# XORXNOR.net
KiCad netlist of a schematic drawn in Altium Designer
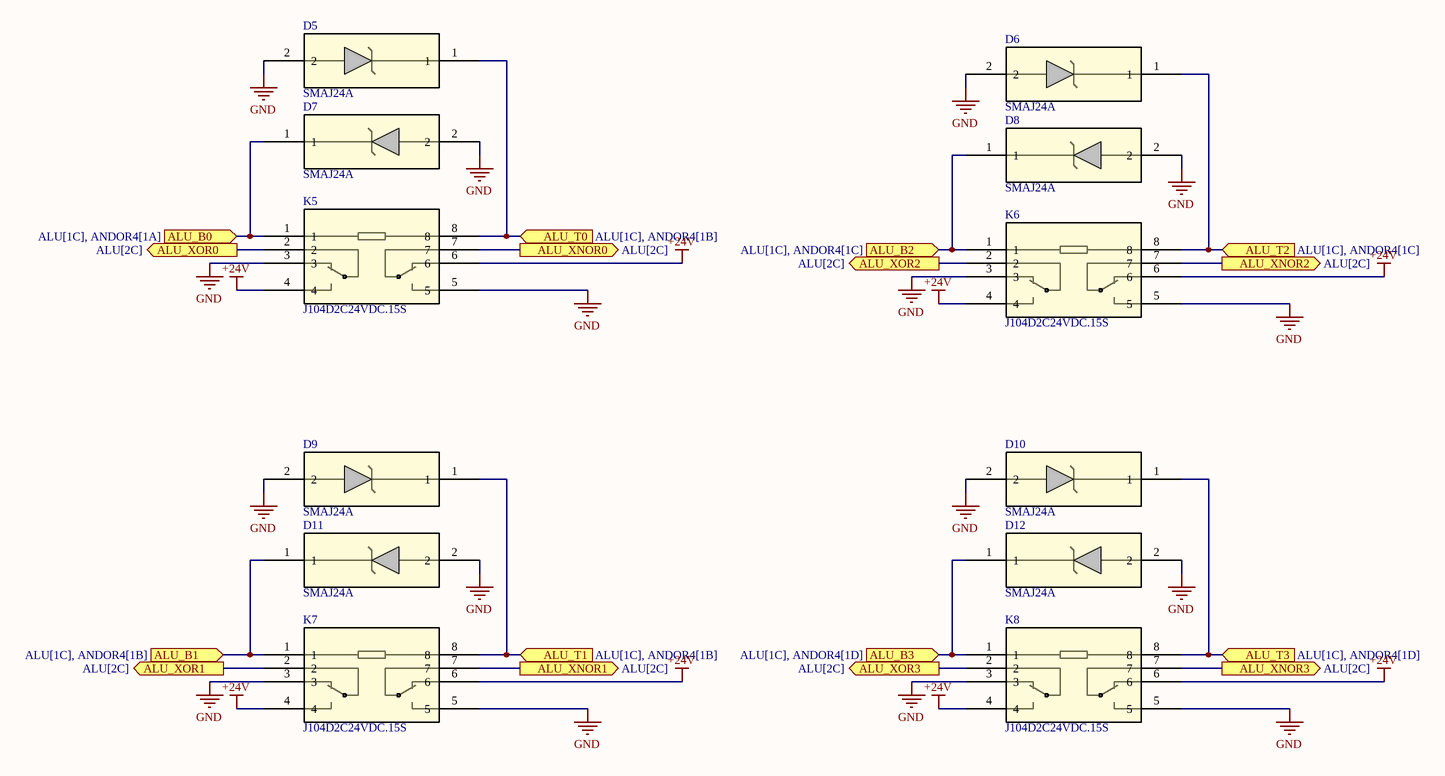
[diagram p0: XORXNOR.SchDoc]

(export (version "E")
  (design (tool "Eeschema 10.0.6"))
  (components
    (comp (ref "D5")
      (value "SMAJ24A")
      (footprint "DI SMAJ24A")
      (description "SMAJ Series 400 W 24 V Uni-Directional Surface Mount TVS Diode - DO-214AC")
      (fields (field (name "MANUFACTURER") "Littelfuse"))
      (libsource (lib "Schlib1") (part "DI SMAJ24A"))
    )
    (comp (ref "D6")
      (value "SMAJ24A")
      (footprint "DI SMAJ24A")
      (description "SMAJ Series 400 W 24 V Uni-Directional Surface Mount TVS Diode - DO-214AC")
      (fields (field (name "MANUFACTURER") "Littelfuse"))
      (libsource (lib "Schlib1") (part "DI SMAJ24A"))
    )
    (comp (ref "D7")
      (value "SMAJ24A")
      (footprint "DI SMAJ24A")
      (description "SMAJ Series 400 W 24 V Uni-Directional Surface Mount TVS Diode - DO-214AC")
      (fields (field (name "MANUFACTURER") "Littelfuse"))
      (libsource (lib "") (part "DI SMAJ24A_1"))
    )
    (comp (ref "D8")
      (value "SMAJ24A")
      (footprint "DI SMAJ24A")
      (description "SMAJ Series 400 W 24 V Uni-Directional Surface Mount TVS Diode - DO-214AC")
      (fields (field (name "MANUFACTURER") "Littelfuse"))
      (libsource (lib "") (part "DI SMAJ24A_1"))
    )
    (comp (ref "D9")
      (value "SMAJ24A")
      (footprint "DI SMAJ24A")
      (description "SMAJ Series 400 W 24 V Uni-Directional Surface Mount TVS Diode - DO-214AC")
      (fields (field (name "MANUFACTURER") "Littelfuse"))
      (libsource (lib "Schlib1") (part "DI SMAJ24A"))
    )
    (comp (ref "D10")
      (value "SMAJ24A")
      (footprint "DI SMAJ24A")
      (description "SMAJ Series 400 W 24 V Uni-Directional Surface Mount TVS Diode - DO-214AC")
      (fields (field (name "MANUFACTURER") "Littelfuse"))
      (libsource (lib "Schlib1") (part "DI SMAJ24A"))
    )
    (comp (ref "D11")
      (value "SMAJ24A")
      (footprint "DI SMAJ24A")
      (description "SMAJ Series 400 W 24 V Uni-Directional Surface Mount TVS Diode - DO-214AC")
      (fields (field (name "MANUFACTURER") "Littelfuse"))
      (libsource (lib "") (part "DI SMAJ24A_1"))
    )
    (comp (ref "D12")
      (value "SMAJ24A")
      (footprint "DI SMAJ24A")
      (description "SMAJ Series 400 W 24 V Uni-Directional Surface Mount TVS Diode - DO-214AC")
      (fields (field (name "MANUFACTURER") "Littelfuse"))
      (libsource (lib "") (part "DI SMAJ24A_1"))
    )
    (comp (ref "K5")
      (value "J104D2C24VDC.15S")
      (footprint "Relay J104D2C24VDC.15S")
      (description "Relay Ul Gen Purp DPDT 2C 24VDC")
      (fields (field (name "MANUFACTURER") "CIT Relay & Switch"))
      (libsource (lib "Schlib1") (part "Relay J104D2C24VDC.15S"))
    )
    (comp (ref "K6")
      (value "J104D2C24VDC.15S")
      (footprint "Relay J104D2C24VDC.15S")
      (description "Relay Ul Gen Purp DPDT 2C 24VDC")
      (fields (field (name "MANUFACTURER") "CIT Relay & Switch"))
      (libsource (lib "Schlib1") (part "Relay J104D2C24VDC.15S"))
    )
    (comp (ref "K7")
      (value "J104D2C24VDC.15S")
      (footprint "Relay J104D2C24VDC.15S")
      (description "Relay Ul Gen Purp DPDT 2C 24VDC")
      (fields (field (name "MANUFACTURER") "CIT Relay & Switch"))
      (libsource (lib "Schlib1") (part "Relay J104D2C24VDC.15S"))
    )
    (comp (ref "K8")
      (value "J104D2C24VDC.15S")
      (footprint "Relay J104D2C24VDC.15S")
      (description "Relay Ul Gen Purp DPDT 2C 24VDC")
      (fields (field (name "MANUFACTURER") "CIT Relay & Switch"))
      (libsource (lib "Schlib1") (part "Relay J104D2C24VDC.15S"))
    )
  )
  (nets
    (net (code "1") (name "+24V") (class "Default")
      (node (ref "K5") (pin "4") (pinfunction "4_4") (pintype "passive"))
      (node (ref "K5") (pin "6") (pinfunction "6_6") (pintype "passive"))
      (node (ref "K6") (pin "4") (pinfunction "4_4") (pintype "passive"))
      (node (ref "K6") (pin "6") (pinfunction "6_6") (pintype "passive"))
      (node (ref "K7") (pin "4") (pinfunction "4_4") (pintype "passive"))
      (node (ref "K7") (pin "6") (pinfunction "6_6") (pintype "passive"))
      (node (ref "K8") (pin "4") (pinfunction "4_4") (pintype "passive"))
      (node (ref "K8") (pin "6") (pinfunction "6_6") (pintype "passive"))
    )
    (net (code "2") (name "/ALU_B0") (class "Default")
      (node (ref "D7") (pin "1") (pinfunction "1_1") (pintype "passive"))
      (node (ref "K5") (pin "1") (pinfunction "1_1") (pintype "passive"))
    )
    (net (code "3") (name "/ALU_B1") (class "Default")
      (node (ref "D11") (pin "1") (pinfunction "1_1") (pintype "passive"))
      (node (ref "K7") (pin "1") (pinfunction "1_1") (pintype "passive"))
    )
    (net (code "4") (name "/ALU_B2") (class "Default")
      (node (ref "D8") (pin "1") (pinfunction "1_1") (pintype "passive"))
      (node (ref "K6") (pin "1") (pinfunction "1_1") (pintype "passive"))
    )
    (net (code "5") (name "/ALU_B3") (class "Default")
      (node (ref "D12") (pin "1") (pinfunction "1_1") (pintype "passive"))
      (node (ref "K8") (pin "1") (pinfunction "1_1") (pintype "passive"))
    )
    (net (code "6") (name "/ALU_T0") (class "Default")
      (node (ref "D5") (pin "1") (pinfunction "1_1") (pintype "passive"))
      (node (ref "K5") (pin "8") (pinfunction "8_8") (pintype "passive"))
    )
    (net (code "7") (name "/ALU_T1") (class "Default")
      (node (ref "D9") (pin "1") (pinfunction "1_1") (pintype "passive"))
      (node (ref "K7") (pin "8") (pinfunction "8_8") (pintype "passive"))
    )
    (net (code "8") (name "/ALU_T2") (class "Default")
      (node (ref "D6") (pin "1") (pinfunction "1_1") (pintype "passive"))
      (node (ref "K6") (pin "8") (pinfunction "8_8") (pintype "passive"))
    )
    (net (code "9") (name "/ALU_T3") (class "Default")
      (node (ref "D10") (pin "1") (pinfunction "1_1") (pintype "passive"))
      (node (ref "K8") (pin "8") (pinfunction "8_8") (pintype "passive"))
    )
    (net (code "10") (name "/ALU_XNOR0") (class "Default")
      (node (ref "K5") (pin "7") (pinfunction "7_7") (pintype "passive"))
    )
    (net (code "11") (name "/ALU_XNOR1") (class "Default")
      (node (ref "K7") (pin "7") (pinfunction "7_7") (pintype "passive"))
    )
    (net (code "12") (name "/ALU_XNOR2") (class "Default")
      (node (ref "K6") (pin "7") (pinfunction "7_7") (pintype "passive"))
    )
    (net (code "13") (name "/ALU_XNOR3") (class "Default")
      (node (ref "K8") (pin "7") (pinfunction "7_7") (pintype "passive"))
    )
    (net (code "14") (name "/ALU_XOR0") (class "Default")
      (node (ref "K5") (pin "2") (pinfunction "2_2") (pintype "passive"))
    )
    (net (code "15") (name "/ALU_XOR1") (class "Default")
      (node (ref "K7") (pin "2") (pinfunction "2_2") (pintype "passive"))
    )
    (net (code "16") (name "/ALU_XOR2") (class "Default")
      (node (ref "K6") (pin "2") (pinfunction "2_2") (pintype "passive"))
    )
    (net (code "17") (name "/ALU_XOR3") (class "Default")
      (node (ref "K8") (pin "2") (pinfunction "2_2") (pintype "passive"))
    )
    (net (code "18") (name "GND") (class "Default")
      (node (ref "D10") (pin "2") (pinfunction "2_2") (pintype "passive"))
      (node (ref "D11") (pin "2") (pinfunction "2_2") (pintype "passive"))
      (node (ref "D12") (pin "2") (pinfunction "2_2") (pintype "passive"))
      (node (ref "D5") (pin "2") (pinfunction "2_2") (pintype "passive"))
      (node (ref "D6") (pin "2") (pinfunction "2_2") (pintype "passive"))
      (node (ref "D7") (pin "2") (pinfunction "2_2") (pintype "passive"))
      (node (ref "D8") (pin "2") (pinfunction "2_2") (pintype "passive"))
      (node (ref "D9") (pin "2") (pinfunction "2_2") (pintype "passive"))
      (node (ref "K5") (pin "3") (pinfunction "3_3") (pintype "passive"))
      (node (ref "K5") (pin "5") (pinfunction "5_5") (pintype "passive"))
      (node (ref "K6") (pin "3") (pinfunction "3_3") (pintype "passive"))
      (node (ref "K6") (pin "5") (pinfunction "5_5") (pintype "passive"))
      (node (ref "K7") (pin "3") (pinfunction "3_3") (pintype "passive"))
      (node (ref "K7") (pin "5") (pinfunction "5_5") (pintype "passive"))
      (node (ref "K8") (pin "3") (pinfunction "3_3") (pintype "passive"))
      (node (ref "K8") (pin "5") (pinfunction "5_5") (pintype "passive"))
    )
  )
)
